# Option_Audio.net
KiCad netlist of a schematic drawn in Altium Designer
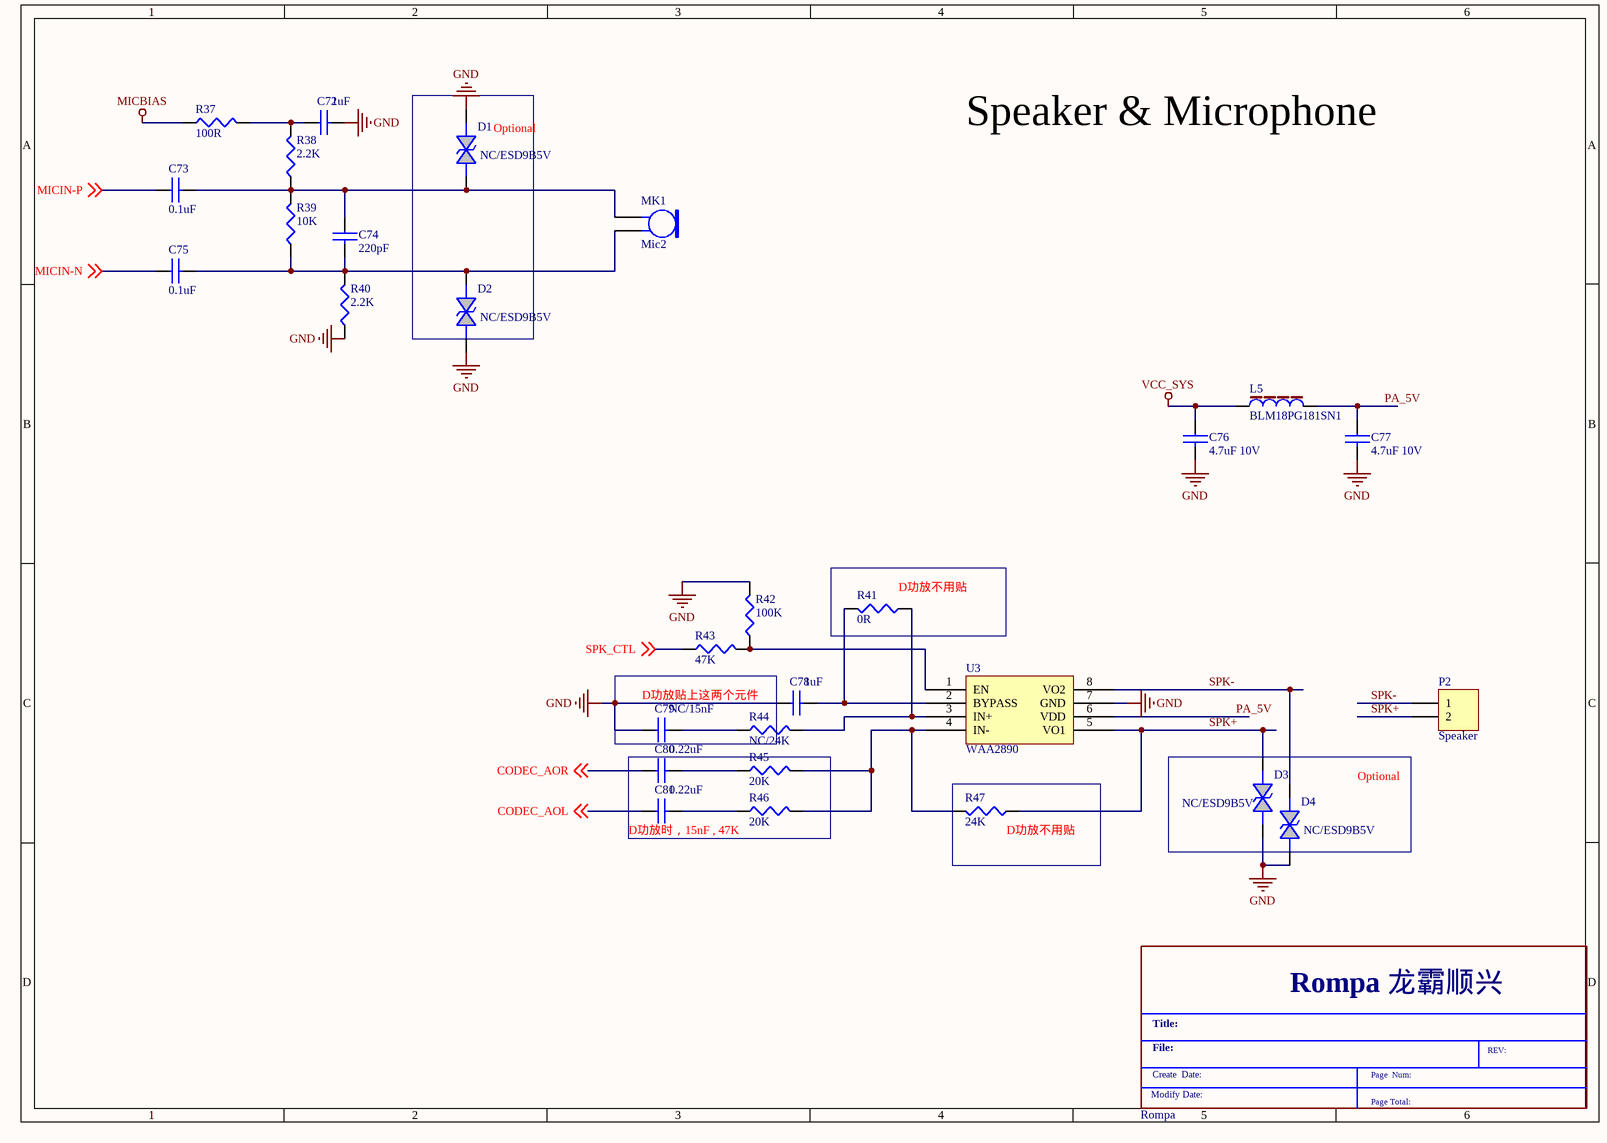
[diagram p0: Option_Audio.SchDoc]

(export (version "E")
  (design (tool "Eeschema 10.0.6"))
  (components
    (comp (ref "C72")
      (value "1uF")
      (footprint "C0402")
      (libsource (lib "RK3128_BETA_V03_20151231_Library") (part "CAP NP"))
    )
    (comp (ref "C73")
      (value "0.1uF")
      (footprint "C0402")
      (libsource (lib "RK3128_BETA_V03_20151231_Library") (part "CAP NP"))
    )
    (comp (ref "C74")
      (value "220pF")
      (footprint "C0402")
      (libsource (lib "RK3128_BETA_V03_20151231_Library") (part "CAP NP"))
    )
    (comp (ref "C75")
      (value "0.1uF")
      (footprint "C0402")
      (libsource (lib "RK3128_BETA_V03_20151231_Library") (part "CAP NP"))
    )
    (comp (ref "C76")
      (value "4.7uF 10V")
      (footprint "C0603")
      (libsource (lib "RK3128_BETA_V03_20151231_Library") (part "CAP NP_Dup1"))
    )
    (comp (ref "C77")
      (value "4.7uF 10V")
      (footprint "C0603")
      (libsource (lib "RK3128_BETA_V03_20151231_Library") (part "CAP NP_Dup1"))
    )
    (comp (ref "C78")
      (value "1uF")
      (footprint "C0402")
      (libsource (lib "RK3128_BETA_V03_20151231_Library") (part "CAP NP"))
    )
    (comp (ref "C79")
      (value "NC/15nF")
      (footprint "C0402")
      (description "%10 10V")
      (libsource (lib "RK3128_BETA_V03_20151231_Library") (part "CAP NP"))
    )
    (comp (ref "C80")
      (value "0.22uF")
      (footprint "C0805")
      (description "10V %10")
      (libsource (lib "RK3128_BETA_V03_20151231_Library") (part "CAP NP"))
    )
    (comp (ref "C81")
      (value "0.22uF")
      (footprint "C0805")
      (description "10V %10")
      (libsource (lib "RK3128_BETA_V03_20151231_Library") (part "CAP NP"))
    )
    (comp (ref "D1")
      (value "NC/ESD9B5V")
      (description "FP:E0402N")
      (libsource (lib "RK3128_BETA_V03_20151231_Library") (part "DIODE BI-DIR TRIG"))
    )
    (comp (ref "D2")
      (value "NC/ESD9B5V")
      (description "FP:E0402N")
      (libsource (lib "RK3128_BETA_V03_20151231_Library") (part "DIODE BI-DIR TRIG"))
    )
    (comp (ref "D3")
      (value "NC/ESD9B5V")
      (description "FP:E0402N")
      (libsource (lib "RK3128_BETA_V03_20151231_Library") (part "DIODE BI-DIR TRIG"))
    )
    (comp (ref "D4")
      (value "NC/ESD9B5V")
      (description "FP:E0402N")
      (libsource (lib "RK3128_BETA_V03_20151231_Library") (part "DIODE BI-DIR TRIG"))
    )
    (comp (ref "L5")
      (value "BLM18PG181SN1")
      (footprint "L0603")
      (libsource (lib "RK3128_BETA_V03_20151231_Library") (part "INDUCTOR_2"))
    )
    (comp (ref "MK1")
      (value "Mic2")
      (footprint "PIN2")
      (description "Microphone")
      (fields (field (name "PUBLISHER") "Altium Limited"))
      (libsource (lib "Miscellaneous Devices") (part "Mic2"))
    )
    (comp (ref "P2")
      (value "Speaker")
      (footprint "HDR1X2")
      (description "Header, 2-Pin")
      (fields (field (name "PUBLISHER") "Altium Limited"))
      (libsource (lib "Miscellaneous Connectors") (part "Header 2"))
    )
    (comp (ref "R37")
      (value "100R")
      (footprint "R0402")
      (libsource (lib "RK3128_BETA_V03_20151231_Library") (part "RESISTOR"))
    )
    (comp (ref "R38")
      (value "2.2K")
      (footprint "R0402")
      (libsource (lib "RK3128_BETA_V03_20151231_Library") (part "RESISTOR"))
    )
    (comp (ref "R39")
      (value "10K")
      (footprint "R0402")
      (libsource (lib "RK3128_BETA_V03_20151231_Library") (part "RESISTOR"))
    )
    (comp (ref "R40")
      (value "2.2K")
      (footprint "R0402")
      (libsource (lib "RK3128_BETA_V03_20151231_Library") (part "RESISTOR"))
    )
    (comp (ref "R41")
      (value "0R")
      (footprint "R0402")
      (libsource (lib "RK3128_BETA_V03_20151231_Library") (part "RESISTOR"))
    )
    (comp (ref "R42")
      (value "100K")
      (footprint "R0402")
      (libsource (lib "RK3128_BETA_V03_20151231_Library") (part "RESISTOR"))
    )
    (comp (ref "R43")
      (value "47K")
      (footprint "R0402")
      (libsource (lib "RK3128_BETA_V03_20151231_Library") (part "RESISTOR"))
    )
    (comp (ref "R44")
      (value "NC/24K")
      (footprint "R0402")
      (description "1/16W %5")
      (libsource (lib "RK3128_BETA_V03_20151231_Library") (part "RESISTOR"))
    )
    (comp (ref "R45")
      (value "20K")
      (footprint "1608[0603]")
      (description "1/16W %5")
      (libsource (lib "RK3128_BETA_V03_20151231_Library") (part "RESISTOR"))
    )
    (comp (ref "R46")
      (value "20K")
      (footprint "1608[0603]")
      (description "1/16W %5")
      (libsource (lib "RK3128_BETA_V03_20151231_Library") (part "RESISTOR"))
    )
    (comp (ref "R47")
      (value "24K")
      (footprint "R0402")
      (libsource (lib "RK3128_BETA_V03_20151231_Library") (part "RESISTOR"))
    )
    (comp (ref "U3") (value "WAA2890") (description "MSOP8") (libsource (lib "*") (part "WAA2890")))
  )
  (nets
    (net (code "1") (name "/PA_5V") (class "Default")
      (node (ref "C77") (pin "1") (pinfunction "1_1") (pintype "passive"))
      (node (ref "L5") (pin "2") (pinfunction "2_2") (pintype "passive"))
      (node (ref "U3") (pin "6") (pinfunction "VDD_6") (pintype "passive"))
    )
    (net (code "2") (name "/SPK+") (class "Default")
      (node (ref "D3") (pin "2") (pinfunction "2_2") (pintype "passive"))
      (node (ref "P2") (pin "2") (pinfunction "2_2") (pintype "passive"))
      (node (ref "R47") (pin "1") (pinfunction "1_1") (pintype "passive"))
      (node (ref "U3") (pin "5") (pinfunction "VO1_5") (pintype "passive"))
    )
    (net (code "3") (name "/SPK-") (class "Default")
      (node (ref "D4") (pin "2") (pinfunction "2_2") (pintype "passive"))
      (node (ref "P2") (pin "1") (pinfunction "1_1") (pintype "passive"))
      (node (ref "U3") (pin "8") (pinfunction "VO2_8") (pintype "passive"))
    )
    (net (code "4") (name "CODEC_AOL") (class "Default")
      (node (ref "C81") (pin "1") (pinfunction "1_1") (pintype "passive"))
    )
    (net (code "5") (name "CODEC_AOR") (class "Default")
      (node (ref "C80") (pin "1") (pinfunction "1_1") (pintype "passive"))
    )
    (net (code "6") (name "GND") (class "Default")
      (node (ref "C72") (pin "2") (pinfunction "2_2") (pintype "passive"))
      (node (ref "C76") (pin "2") (pinfunction "2_2") (pintype "passive"))
      (node (ref "C77") (pin "2") (pinfunction "2_2") (pintype "passive"))
      (node (ref "C78") (pin "1") (pinfunction "1_1") (pintype "passive"))
      (node (ref "C79") (pin "1") (pinfunction "1_1") (pintype "passive"))
      (node (ref "D1") (pin "2") (pinfunction "2_2") (pintype "passive"))
      (node (ref "D2") (pin "1") (pinfunction "1_1") (pintype "passive"))
      (node (ref "D3") (pin "1") (pinfunction "1_1") (pintype "passive"))
      (node (ref "D4") (pin "1") (pinfunction "1_1") (pintype "passive"))
      (node (ref "R40") (pin "1") (pinfunction "1_1") (pintype "passive"))
      (node (ref "R42") (pin "2") (pinfunction "2_2") (pintype "passive"))
      (node (ref "U3") (pin "7") (pinfunction "GND_7") (pintype "passive"))
    )
    (net (code "7") (name "MICBIAS") (class "Default")
      (node (ref "R37") (pin "1") (pinfunction "1_1") (pintype "passive"))
    )
    (net (code "8") (name "MICIN-N") (class "Default")
      (node (ref "C75") (pin "1") (pinfunction "1_1") (pintype "passive"))
    )
    (net (code "9") (name "MICIN-P") (class "Default")
      (node (ref "C73") (pin "1") (pinfunction "1_1") (pintype "passive"))
    )
    (net (code "10") (name "Net-(C72-Pad1)") (class "Default")
      (node (ref "C72") (pin "1") (pinfunction "1_1") (pintype "passive"))
      (node (ref "R37") (pin "2") (pinfunction "2_2") (pintype "passive"))
      (node (ref "R38") (pin "2") (pinfunction "2_2") (pintype "passive"))
    )
    (net (code "11") (name "Net-(C73-Pad2)") (class "Default")
      (node (ref "C73") (pin "2") (pinfunction "2_2") (pintype "passive"))
      (node (ref "C74") (pin "1") (pinfunction "1_1") (pintype "passive"))
      (node (ref "D1") (pin "1") (pinfunction "1_1") (pintype "passive"))
      (node (ref "MK1") (pin "1") (pinfunction "1_1") (pintype "passive"))
      (node (ref "R38") (pin "1") (pinfunction "1_1") (pintype "passive"))
      (node (ref "R39") (pin "2") (pinfunction "2_2") (pintype "passive"))
    )
    (net (code "12") (name "Net-(C74-Pad2)") (class "Default")
      (node (ref "C74") (pin "2") (pinfunction "2_2") (pintype "passive"))
      (node (ref "C75") (pin "2") (pinfunction "2_2") (pintype "passive"))
      (node (ref "D2") (pin "2") (pinfunction "2_2") (pintype "passive"))
      (node (ref "MK1") (pin "2") (pinfunction "2_2") (pintype "passive"))
      (node (ref "R39") (pin "1") (pinfunction "1_1") (pintype "passive"))
      (node (ref "R40") (pin "2") (pinfunction "2_2") (pintype "passive"))
    )
    (net (code "13") (name "Net-(C79-Pad2)") (class "Default")
      (node (ref "C79") (pin "2") (pinfunction "2_2") (pintype "passive"))
      (node (ref "R44") (pin "1") (pinfunction "1_1") (pintype "passive"))
    )
    (net (code "14") (name "Net-(C80-Pad2)") (class "Default")
      (node (ref "C80") (pin "2") (pinfunction "2_2") (pintype "passive"))
      (node (ref "R45") (pin "1") (pinfunction "1_1") (pintype "passive"))
    )
    (net (code "15") (name "Net-(C81-Pad2)") (class "Default")
      (node (ref "C81") (pin "2") (pinfunction "2_2") (pintype "passive"))
      (node (ref "R46") (pin "1") (pinfunction "1_1") (pintype "passive"))
    )
    (net (code "16") (name "Net-(U3-BYPASS)") (class "Default")
      (node (ref "C78") (pin "2") (pinfunction "2_2") (pintype "passive"))
      (node (ref "R41") (pin "2") (pinfunction "2_2") (pintype "passive"))
      (node (ref "U3") (pin "2") (pinfunction "BYPASS_2") (pintype "passive"))
    )
    (net (code "17") (name "Net-(U3-EN)") (class "Default")
      (node (ref "R42") (pin "1") (pinfunction "1_1") (pintype "passive"))
      (node (ref "R43") (pin "2") (pinfunction "2_2") (pintype "passive"))
      (node (ref "U3") (pin "1") (pinfunction "EN_1") (pintype "passive"))
    )
    (net (code "18") (name "Net-(U3-IN+)") (class "Default")
      (node (ref "R41") (pin "1") (pinfunction "1_1") (pintype "passive"))
      (node (ref "R44") (pin "2") (pinfunction "2_2") (pintype "passive"))
      (node (ref "U3") (pin "3") (pinfunction "IN+_3") (pintype "passive"))
    )
    (net (code "19") (name "Net-(U3-IN-)") (class "Default")
      (node (ref "R45") (pin "2") (pinfunction "2_2") (pintype "passive"))
      (node (ref "R46") (pin "2") (pinfunction "2_2") (pintype "passive"))
      (node (ref "R47") (pin "2") (pinfunction "2_2") (pintype "passive"))
      (node (ref "U3") (pin "4") (pinfunction "IN-_4") (pintype "passive"))
    )
    (net (code "20") (name "SPK_CTL") (class "Default")
      (node (ref "R43") (pin "1") (pinfunction "1_1") (pintype "passive"))
    )
    (net (code "21") (name "VCC_SYS") (class "Default")
      (node (ref "C76") (pin "1") (pinfunction "1_1") (pintype "passive"))
      (node (ref "L5") (pin "1") (pinfunction "1_1") (pintype "passive"))
    )
  )
)
